# Thermo.net
KiCad netlist of a schematic drawn in Altium Designer
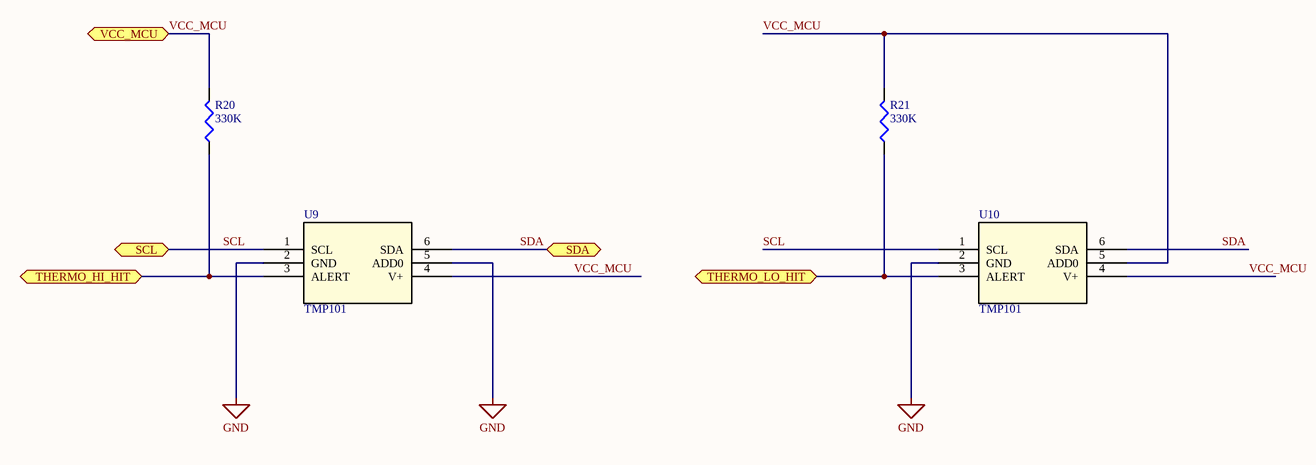
[diagram p0: Thermo.SchDoc]

(export (version "E")
  (design (tool "Eeschema 10.0.6"))
  (components
    (comp (ref "R20")
      (value "330K")
      (footprint "clock:0603")
      (description "Resistor")
      (fields (field (name "Comment") "Res3") (field (name "PUBLISHER") "Altium Limited"))
      (libsource (lib "Miscellaneous Devices") (part "Res3"))
    )
    (comp (ref "R21")
      (value "330K")
      (footprint "clock:0603")
      (description "Resistor")
      (fields (field (name "Comment") "Res3") (field (name "PUBLISHER") "Altium Limited"))
      (libsource (lib "Miscellaneous Devices") (part "Res3"))
    )
    (comp (ref "U9")
      (value "TMP101")
      (footprint "clock:SOT23-6")
      (description "Imported")
      (fields
        (field (name "MANUFACTURER_PART_NUMBER") "tmp101_dbv_6")
        (field (name "MANUFACTURER") "Texas Instruments")
      )
      (libsource (lib "clock") (part "TMP101"))
    )
    (comp (ref "U10")
      (value "TMP101")
      (footprint "clock:SOT23-6")
      (description "Imported")
      (fields
        (field (name "MANUFACTURER_PART_NUMBER") "tmp101_dbv_6")
        (field (name "MANUFACTURER") "Texas Instruments")
      )
      (libsource (lib "clock") (part "TMP101"))
    )
  )
  (nets
    (net (code "1") (name "/SCL") (class "Default")
      (node (ref "U10") (pin "1") (pinfunction "SCL_1") (pintype "passive"))
      (node (ref "U9") (pin "1") (pinfunction "SCL_1") (pintype "passive"))
    )
    (net (code "2") (name "/SDA") (class "Default")
      (node (ref "U10") (pin "6") (pinfunction "SDA_6") (pintype "passive"))
      (node (ref "U9") (pin "6") (pinfunction "SDA_6") (pintype "passive"))
    )
    (net (code "3") (name "/THERMO_HI_HIT") (class "Default")
      (node (ref "R20") (pin "1") (pinfunction "1_1") (pintype "passive"))
      (node (ref "U9") (pin "3") (pinfunction "ALERT_3") (pintype "passive"))
    )
    (net (code "4") (name "/THERMO_LO_HIT") (class "Default")
      (node (ref "R21") (pin "1") (pinfunction "1_1") (pintype "passive"))
      (node (ref "U10") (pin "3") (pinfunction "ALERT_3") (pintype "passive"))
    )
    (net (code "5") (name "/VCC_MCU") (class "Default")
      (node (ref "R20") (pin "2") (pinfunction "2_2") (pintype "passive"))
      (node (ref "R21") (pin "2") (pinfunction "2_2") (pintype "passive"))
      (node (ref "U10") (pin "4") (pinfunction "V+_4") (pintype "passive"))
      (node (ref "U10") (pin "5") (pinfunction "ADD0_5") (pintype "passive"))
      (node (ref "U9") (pin "4") (pinfunction "V+_4") (pintype "passive"))
    )
    (net (code "6") (name "GND") (class "Default")
      (node (ref "U10") (pin "2") (pinfunction "GND_2") (pintype "passive"))
      (node (ref "U9") (pin "2") (pinfunction "GND_2") (pintype "passive"))
      (node (ref "U9") (pin "5") (pinfunction "ADD0_5") (pintype "passive"))
    )
  )
)
